# channel-link-test-board.net
KiCad netlist of a schematic drawn in EAGLE
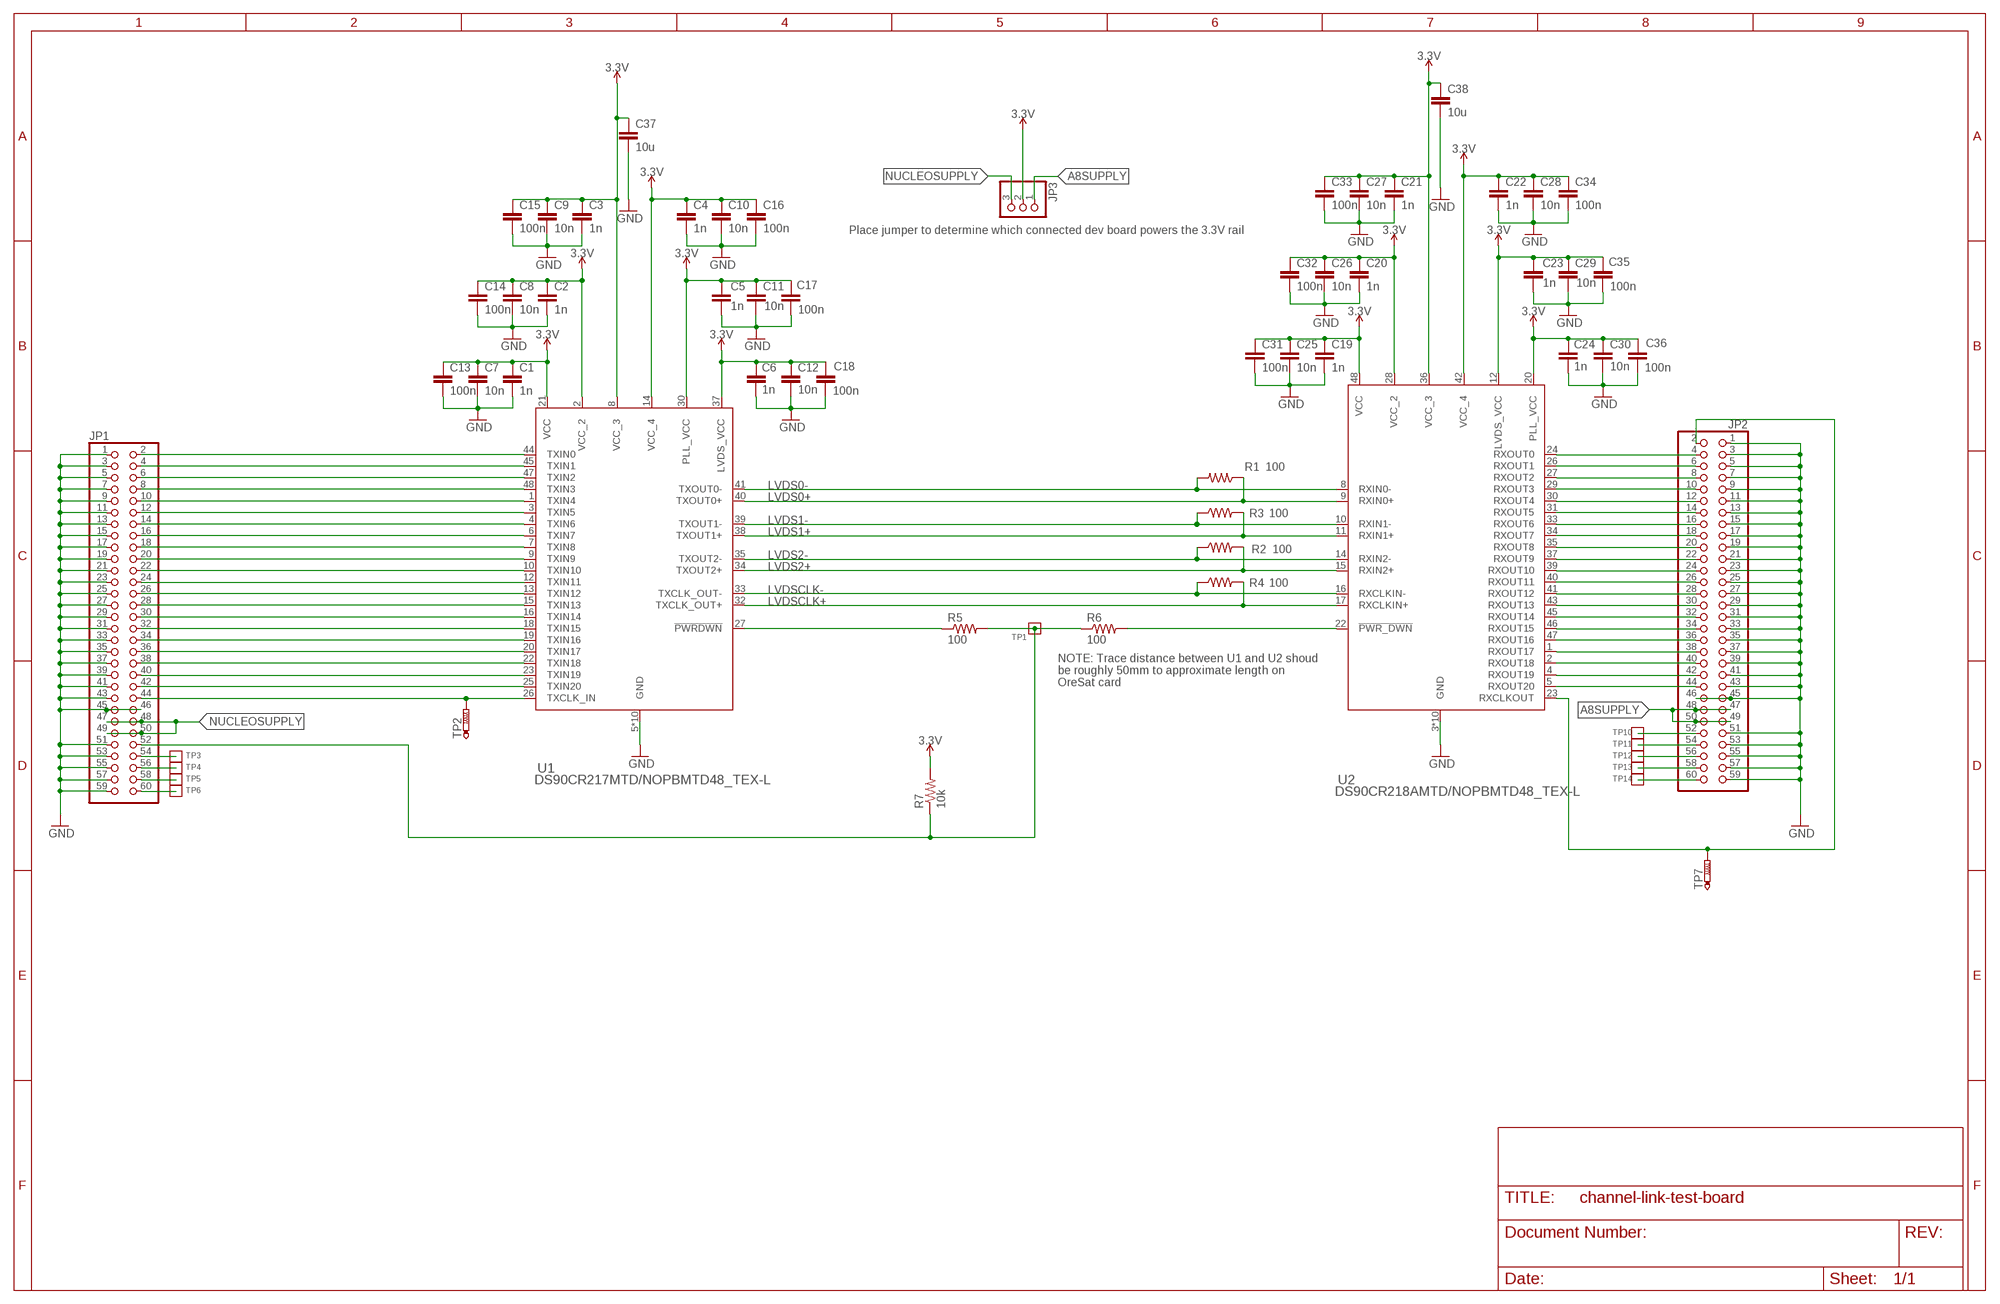
[diagram p0: schematic, sheet 1]

(export (version "E")
  (design (tool "Eeschema 10.0.6"))
  (components
    (comp (ref "C1")
      (value "1n")
      (footprint "eagle-import:.0402-C-NOSILK")
      (fields (field (name "MFR") "Murata") (field (name "MPN") "GRM155R71H102KA01J"))
      (libsource (lib "eagle-import") (part "C-EU0402-C-NOSILK"))
    )
    (comp (ref "C2")
      (value "1n")
      (footprint "eagle-import:.0402-C-NOSILK")
      (fields (field (name "MFR") "Murata") (field (name "MPN") "GRM155R71H102KA01J"))
      (libsource (lib "eagle-import") (part "C-EU0402-C-NOSILK"))
    )
    (comp (ref "C3")
      (value "1n")
      (footprint "eagle-import:.0402-C-NOSILK")
      (fields (field (name "MFR") "Murata") (field (name "MPN") "GRM155R71H102KA01J"))
      (libsource (lib "eagle-import") (part "C-EU0402-C-NOSILK"))
    )
    (comp (ref "C4")
      (value "1n")
      (footprint "eagle-import:.0402-C-NOSILK")
      (fields (field (name "MFR") "Murata") (field (name "MPN") "GRM155R71H102KA01J"))
      (libsource (lib "eagle-import") (part "C-EU0402-C-NOSILK"))
    )
    (comp (ref "C5")
      (value "1n")
      (footprint "eagle-import:.0402-C-NOSILK")
      (fields (field (name "MFR") "Murata") (field (name "MPN") "GRM155R71H102KA01J"))
      (libsource (lib "eagle-import") (part "C-EU0402-C-NOSILK"))
    )
    (comp (ref "C6")
      (value "1n")
      (footprint "eagle-import:.0402-C-NOSILK")
      (fields (field (name "MFR") "Murata") (field (name "MPN") "GRM155R71H102KA01J"))
      (libsource (lib "eagle-import") (part "C-EU0402-C-NOSILK"))
    )
    (comp (ref "C7")
      (value "10n")
      (footprint "eagle-import:.0603-C-NOSILK")
      (fields (field (name "MFR") "Kemet") (field (name "MPN") "C0603C103M5RACTU"))
      (libsource (lib "eagle-import") (part "C-EU0603-C-NOSILK"))
    )
    (comp (ref "C8")
      (value "10n")
      (footprint "eagle-import:.0603-C-NOSILK")
      (fields (field (name "MFR") "Kemet") (field (name "MPN") "C0603C103M5RACTU"))
      (libsource (lib "eagle-import") (part "C-EU0603-C-NOSILK"))
    )
    (comp (ref "C9")
      (value "10n")
      (footprint "eagle-import:.0603-C-NOSILK")
      (fields (field (name "MFR") "Kemet") (field (name "MPN") "C0603C103M5RACTU"))
      (libsource (lib "eagle-import") (part "C-EU0603-C-NOSILK"))
    )
    (comp (ref "C10")
      (value "10n")
      (footprint "eagle-import:.0603-C-NOSILK")
      (fields (field (name "MFR") "Kemet") (field (name "MPN") "C0603C103M5RACTU"))
      (libsource (lib "eagle-import") (part "C-EU0603-C-NOSILK"))
    )
    (comp (ref "C11")
      (value "10n")
      (footprint "eagle-import:.0603-C-NOSILK")
      (fields (field (name "MFR") "Kemet") (field (name "MPN") "C0603C103M5RACTU"))
      (libsource (lib "eagle-import") (part "C-EU0603-C-NOSILK"))
    )
    (comp (ref "C12")
      (value "10n")
      (footprint "eagle-import:.0402-C-NOSILK")
      (fields (field (name "MFR") "Kemet") (field (name "MPN") "C0603C103M5RACTU"))
      (libsource (lib "eagle-import") (part "C-EU0402-C-NOSILK"))
    )
    (comp (ref "C13")
      (value "100n")
      (footprint "eagle-import:.0805-C-NOSILK")
      (fields (field (name "MFR") "Kemet") (field (name "MPN") "C0805C104Z5VACTU"))
      (libsource (lib "eagle-import") (part "C-EU0805-C-NOSILK"))
    )
    (comp (ref "C14")
      (value "100n")
      (footprint "eagle-import:.0402-C-NOSILK")
      (fields (field (name "MFR") "Kemet") (field (name "MPN") "C0805C104Z5VACTU"))
      (libsource (lib "eagle-import") (part "C-EU0402-C-NOSILK"))
    )
    (comp (ref "C15")
      (value "100n")
      (footprint "eagle-import:.0805-C-NOSILK")
      (fields (field (name "MFR") "Kemet") (field (name "MPN") "C0805C104Z5VACTU"))
      (libsource (lib "eagle-import") (part "C-EU0805-C-NOSILK"))
    )
    (comp (ref "C16")
      (value "100n")
      (footprint "eagle-import:.0805-C-NOSILK")
      (fields (field (name "MFR") "Kemet") (field (name "MPN") "C0805C104Z5VACTU"))
      (libsource (lib "eagle-import") (part "C-EU0805-C-NOSILK"))
    )
    (comp (ref "C17")
      (value "100n")
      (footprint "eagle-import:.0805-C-NOSILK")
      (fields (field (name "MFR") "Kemet") (field (name "MPN") "C0805C104Z5VACTU"))
      (libsource (lib "eagle-import") (part "C-EU0805-C-NOSILK"))
    )
    (comp (ref "C18")
      (value "100n")
      (footprint "eagle-import:.0805-C-NOSILK")
      (fields (field (name "MFR") "Kemet") (field (name "MPN") "C0805C104Z5VACTU"))
      (libsource (lib "eagle-import") (part "C-EU0805-C-NOSILK"))
    )
    (comp (ref "C19")
      (value "1n")
      (footprint "eagle-import:.0402-C-NOSILK")
      (fields (field (name "MFR") "Murata") (field (name "MPN") "GRM155R71H102KA01J"))
      (libsource (lib "eagle-import") (part "C-EU0402-C-NOSILK"))
    )
    (comp (ref "C20")
      (value "1n")
      (footprint "eagle-import:.0402-C-NOSILK")
      (fields (field (name "MFR") "Murata") (field (name "MPN") "GRM155R71H102KA01J"))
      (libsource (lib "eagle-import") (part "C-EU0402-C-NOSILK"))
    )
    (comp (ref "C21")
      (value "1n")
      (footprint "eagle-import:.0402-C-NOSILK")
      (fields (field (name "MFR") "Murata") (field (name "MPN") "GRM155R71H102KA01J"))
      (libsource (lib "eagle-import") (part "C-EU0402-C-NOSILK"))
    )
    (comp (ref "C22")
      (value "1n")
      (footprint "eagle-import:.0402-C-NOSILK")
      (fields (field (name "MFR") "Murata") (field (name "MPN") "GRM155R71H102KA01J"))
      (libsource (lib "eagle-import") (part "C-EU0402-C-NOSILK"))
    )
    (comp (ref "C23")
      (value "1n")
      (footprint "eagle-import:.0402-C-NOSILK")
      (fields (field (name "MFR") "Murata") (field (name "MPN") "GRM155R71H102KA01J"))
      (libsource (lib "eagle-import") (part "C-EU0402-C-NOSILK"))
    )
    (comp (ref "C24")
      (value "1n")
      (footprint "eagle-import:.0402-C-NOSILK")
      (fields (field (name "MFR") "Murata") (field (name "MPN") "GRM155R71H102KA01J"))
      (libsource (lib "eagle-import") (part "C-EU0402-C-NOSILK"))
    )
    (comp (ref "C25")
      (value "10n")
      (footprint "eagle-import:.0402-C-NOSILK")
      (fields (field (name "MFR") "Kemet") (field (name "MPN") "C0603C103M5RACTU"))
      (libsource (lib "eagle-import") (part "C-EU0402-C-NOSILK"))
    )
    (comp (ref "C26")
      (value "10n")
      (footprint "eagle-import:.0603-C-NOSILK")
      (fields (field (name "MFR") "Kemet") (field (name "MPN") "C0603C103M5RACTU"))
      (libsource (lib "eagle-import") (part "C-EU0603-C-NOSILK"))
    )
    (comp (ref "C27")
      (value "10n")
      (footprint "eagle-import:.0603-C-NOSILK")
      (fields (field (name "MFR") "Kemet") (field (name "MPN") "C0603C103M5RACTU"))
      (libsource (lib "eagle-import") (part "C-EU0603-C-NOSILK"))
    )
    (comp (ref "C28")
      (value "10n")
      (footprint "eagle-import:.0603-C-NOSILK")
      (fields (field (name "MFR") "Kemet") (field (name "MPN") "C0603C103M5RACTU"))
      (libsource (lib "eagle-import") (part "C-EU0603-C-NOSILK"))
    )
    (comp (ref "C29")
      (value "10n")
      (footprint "eagle-import:.0603-C-NOSILK")
      (fields (field (name "MFR") "Kemet") (field (name "MPN") "C0603C103M5RACTU"))
      (libsource (lib "eagle-import") (part "C-EU0603-C-NOSILK"))
    )
    (comp (ref "C30")
      (value "10n")
      (footprint "eagle-import:.0603-C-NOSILK")
      (fields (field (name "MFR") "Kemet") (field (name "MPN") "C0603C103M5RACTU"))
      (libsource (lib "eagle-import") (part "C-EU0603-C-NOSILK"))
    )
    (comp (ref "C31")
      (value "100n")
      (footprint "eagle-import:.0402-C-NOSILK")
      (fields (field (name "MFR") "Kemet") (field (name "MPN") "C0805C104Z5VACTU"))
      (libsource (lib "eagle-import") (part "C-EU0402-C-NOSILK"))
    )
    (comp (ref "C32")
      (value "100n")
      (footprint "eagle-import:.0805-C-NOSILK")
      (fields (field (name "MFR") "Kemet") (field (name "MPN") "C0805C104Z5VACTU"))
      (libsource (lib "eagle-import") (part "C-EU0805-C-NOSILK"))
    )
    (comp (ref "C33")
      (value "100n")
      (footprint "eagle-import:.0805-C-NOSILK")
      (fields (field (name "MFR") "Kemet") (field (name "MPN") "C0805C104Z5VACTU"))
      (libsource (lib "eagle-import") (part "C-EU0805-C-NOSILK"))
    )
    (comp (ref "C34")
      (value "100n")
      (footprint "eagle-import:.0805-C-NOSILK")
      (fields (field (name "MFR") "Kemet") (field (name "MPN") "C0805C104Z5VACTU"))
      (libsource (lib "eagle-import") (part "C-EU0805-C-NOSILK"))
    )
    (comp (ref "C35")
      (value "100n")
      (footprint "eagle-import:.0805-C-NOSILK")
      (fields (field (name "MFR") "Kemet") (field (name "MPN") "C0805C104Z5VACTU"))
      (libsource (lib "eagle-import") (part "C-EU0805-C-NOSILK"))
    )
    (comp (ref "C36")
      (value "100n")
      (footprint "eagle-import:.0805-C-NOSILK")
      (fields (field (name "MFR") "Kemet") (field (name "MPN") "C0805C104Z5VACTU"))
      (libsource (lib "eagle-import") (part "C-EU0805-C-NOSILK"))
    )
    (comp (ref "C37")
      (value "10u")
      (footprint "eagle-import:.0603-C-NOSILK")
      (fields (field (name "MFR") "Murata") (field (name "MPN") "GRM188R61A106KE69J"))
      (libsource (lib "eagle-import") (part "C-EU0603-C-NOSILK"))
    )
    (comp (ref "C38")
      (value "10u")
      (footprint "eagle-import:.0603-C-NOSILK")
      (fields (field (name "MFR") "Murata") (field (name "MPN") "GRM188R61A106KE69J"))
      (libsource (lib "eagle-import") (part "C-EU0603-C-NOSILK"))
    )
    (comp (ref "JP1")
      (value "PINHD-2X30")
      (footprint "eagle-import:2X30")
      (fields (field (name "MFR") "Amphenol") (field (name "MPN") "71918-160LF"))
      (libsource (lib "eagle-import") (part "PINHD-2X30"))
    )
    (comp (ref "JP2")
      (value "PINHD-2X30")
      (footprint "eagle-import:2X30")
      (fields (field (name "MFR") "Amphenol") (field (name "MPN") "71918-160LF"))
      (libsource (lib "eagle-import") (part "PINHD-2X30"))
    )
    (comp (ref "JP3")
      (value "PINHD-1X3")
      (footprint "eagle-import:1X03")
      (fields (field (name "MFR") "Wurth") (field (name "MPN") "61300311121"))
      (libsource (lib "eagle-import") (part "PINHD-1X3"))
    )
    (comp (ref "R1")
      (value "100")
      (footprint "eagle-import:.0201-C-NOSILK")
      (fields (field (name "MFR") "Yageo") (field (name "MPN") "RC0201FR-07100RL"))
      (libsource (lib "eagle-import") (part "R-US_0201-C-NOSILK"))
    )
    (comp (ref "R2")
      (value "100")
      (footprint "eagle-import:.0201-C-NOSILK")
      (fields (field (name "MFR") "Yageo") (field (name "MPN") "RC0201FR-07100RL"))
      (libsource (lib "eagle-import") (part "R-US_0201-C-NOSILK"))
    )
    (comp (ref "R3")
      (value "100")
      (footprint "eagle-import:.0201-C-NOSILK")
      (fields (field (name "MFR") "Yageo") (field (name "MPN") "RC0201FR-07100RL"))
      (libsource (lib "eagle-import") (part "R-US_0201-C-NOSILK"))
    )
    (comp (ref "R4")
      (value "100")
      (footprint "eagle-import:.0201-C-NOSILK")
      (fields (field (name "MFR") "Yageo") (field (name "MPN") "RC0201FR-07100RL"))
      (libsource (lib "eagle-import") (part "R-US_0201-C-NOSILK"))
    )
    (comp (ref "R5")
      (value "100")
      (footprint "eagle-import:.0603-C-NOSILK")
      (fields (field (name "MFR") "Yageo") (field (name "MPN") "RC0603FR-07100RL"))
      (libsource (lib "eagle-import") (part "R-US_0603-C-NOSILK"))
    )
    (comp (ref "R6")
      (value "100")
      (footprint "eagle-import:.0603-C-NOSILK")
      (fields (field (name "MFR") "Yageo") (field (name "MPN") "RC0603FR-07100RL"))
      (libsource (lib "eagle-import") (part "R-US_0603-C-NOSILK"))
    )
    (comp (ref "R7")
      (value "10k")
      (footprint "eagle-import:.0603-C-NOSILK")
      (fields (field (name "MFR") "Yageo") (field (name "MPN") "RC0603FR-0710KL"))
      (libsource (lib "eagle-import") (part "R-US_0603-C-NOSILK"))
    )
    (comp (ref "TP1")
      (value "TEST-POINT-LARGE-SQUARE")
      (footprint "eagle-import:1X01")
      (libsource (lib "eagle-import") (part "TEST-POINT-LARGE-SQUARE"))
    )
    (comp (ref "TP2")
      (value "PTR1B2,54")
      (footprint "eagle-import:B2,54")
      (libsource (lib "eagle-import") (part "PTR1B2,54"))
    )
    (comp (ref "TP3")
      (value "TEST-POINT-LARGE-SQUARE")
      (footprint "eagle-import:1X01")
      (libsource (lib "eagle-import") (part "TEST-POINT-LARGE-SQUARE"))
    )
    (comp (ref "TP4")
      (value "TEST-POINT-LARGE-SQUARE")
      (footprint "eagle-import:1X01")
      (libsource (lib "eagle-import") (part "TEST-POINT-LARGE-SQUARE"))
    )
    (comp (ref "TP5")
      (value "TEST-POINT-LARGE-SQUARE")
      (footprint "eagle-import:1X01")
      (libsource (lib "eagle-import") (part "TEST-POINT-LARGE-SQUARE"))
    )
    (comp (ref "TP6")
      (value "TEST-POINT-LARGE-SQUARE")
      (footprint "eagle-import:1X01")
      (libsource (lib "eagle-import") (part "TEST-POINT-LARGE-SQUARE"))
    )
    (comp (ref "TP7")
      (value "PTR1B2,54")
      (footprint "eagle-import:B2,54")
      (libsource (lib "eagle-import") (part "PTR1B2,54"))
    )
    (comp (ref "TP10")
      (value "TEST-POINT-LARGE-SQUARE")
      (footprint "eagle-import:1X01")
      (libsource (lib "eagle-import") (part "TEST-POINT-LARGE-SQUARE"))
    )
    (comp (ref "TP11")
      (value "TEST-POINT-LARGE-SQUARE")
      (footprint "eagle-import:1X01")
      (libsource (lib "eagle-import") (part "TEST-POINT-LARGE-SQUARE"))
    )
    (comp (ref "TP12")
      (value "TEST-POINT-LARGE-SQUARE")
      (footprint "eagle-import:1X01")
      (libsource (lib "eagle-import") (part "TEST-POINT-LARGE-SQUARE"))
    )
    (comp (ref "TP13")
      (value "TEST-POINT-LARGE-SQUARE")
      (footprint "eagle-import:1X01")
      (libsource (lib "eagle-import") (part "TEST-POINT-LARGE-SQUARE"))
    )
    (comp (ref "TP14")
      (value "TEST-POINT-LARGE-SQUARE")
      (footprint "eagle-import:1X01")
      (libsource (lib "eagle-import") (part "TEST-POINT-LARGE-SQUARE"))
    )
    (comp (ref "U1")
      (value "DS90CR217MTD/NOPBMTD48_TEX-L")
      (footprint "eagle-import:MTD48_TEX-L")
      (fields (field (name "MFR") "Texas Instruments") (field (name "MPN") "DS90CR218AMTD/NOPB"))
      (libsource (lib "eagle-import") (part "DS90CR217MTD/NOPBMTD48_TEX-L"))
    )
    (comp (ref "U2")
      (value "DS90CR218AMTD/NOPBMTD48_TEX-L")
      (footprint "eagle-import:MTD48_TEX-L")
      (fields (field (name "MFR") "Texas Instruments") (field (name "MPN") "DS90CR218AMTD/NOPB"))
      (libsource (lib "eagle-import") (part "DS90CR218AMTD/NOPBMTD48_TEX-L"))
    )
  )
  (nets
    (net (code "1") (name "/LVDS0+") (class "Default")
      (node (ref "R1") (pin "1") (pinfunction "1_1") (pintype "passive"))
      (node (ref "U1") (pin "40") (pinfunction "TXOUT0+_40") (pintype "output"))
      (node (ref "U2") (pin "9") (pinfunction "RXIN0+_9") (pintype "input"))
    )
    (net (code "2") (name "/LVDS0-") (class "Default")
      (node (ref "R1") (pin "2") (pinfunction "2_2") (pintype "passive"))
      (node (ref "U1") (pin "41") (pinfunction "TXOUT0-_41") (pintype "output"))
      (node (ref "U2") (pin "8") (pinfunction "RXIN0-_8") (pintype "input"))
    )
    (net (code "3") (name "/LVDS1+") (class "Default")
      (node (ref "R3") (pin "2") (pinfunction "2_2") (pintype "passive"))
      (node (ref "U1") (pin "38") (pinfunction "TXOUT1+_38") (pintype "output"))
      (node (ref "U2") (pin "11") (pinfunction "RXIN1+_11") (pintype "input"))
    )
    (net (code "4") (name "/LVDS1-") (class "Default")
      (node (ref "R3") (pin "1") (pinfunction "1_1") (pintype "passive"))
      (node (ref "U1") (pin "39") (pinfunction "TXOUT1-_39") (pintype "output"))
      (node (ref "U2") (pin "10") (pinfunction "RXIN1-_10") (pintype "input"))
    )
    (net (code "5") (name "/LVDS2+") (class "Default")
      (node (ref "R2") (pin "2") (pinfunction "2_2") (pintype "passive"))
      (node (ref "U1") (pin "34") (pinfunction "TXOUT2+_34") (pintype "output"))
      (node (ref "U2") (pin "15") (pinfunction "RXIN2+_15") (pintype "input"))
    )
    (net (code "6") (name "/LVDS2-") (class "Default")
      (node (ref "R2") (pin "1") (pinfunction "1_1") (pintype "passive"))
      (node (ref "U1") (pin "35") (pinfunction "TXOUT2-_35") (pintype "output"))
      (node (ref "U2") (pin "14") (pinfunction "RXIN2-_14") (pintype "input"))
    )
    (net (code "7") (name "/LVDSCLK+") (class "Default")
      (node (ref "R4") (pin "2") (pinfunction "2_2") (pintype "passive"))
      (node (ref "U1") (pin "32") (pinfunction "TXCLK_OUT+_32") (pintype "output"))
      (node (ref "U2") (pin "17") (pinfunction "RXCLKIN+_17") (pintype "input"))
    )
    (net (code "8") (name "/LVDSCLK-") (class "Default")
      (node (ref "R4") (pin "1") (pinfunction "1_1") (pintype "passive"))
      (node (ref "U1") (pin "33") (pinfunction "TXCLK_OUT-_33") (pintype "output"))
      (node (ref "U2") (pin "16") (pinfunction "RXCLKIN-_16") (pintype "input"))
    )
    (net (code "9") (name "3.3V") (class "Default")
      (node (ref "C1") (pin "1") (pinfunction "1_1") (pintype "passive"))
      (node (ref "C10") (pin "1") (pinfunction "1_1") (pintype "passive"))
      (node (ref "C11") (pin "1") (pinfunction "1_1") (pintype "passive"))
      (node (ref "C12") (pin "1") (pinfunction "1_1") (pintype "passive"))
      (node (ref "C13") (pin "1") (pinfunction "1_1") (pintype "passive"))
      (node (ref "C14") (pin "1") (pinfunction "1_1") (pintype "passive"))
      (node (ref "C15") (pin "1") (pinfunction "1_1") (pintype "passive"))
      (node (ref "C16") (pin "1") (pinfunction "1_1") (pintype "passive"))
      (node (ref "C17") (pin "1") (pinfunction "1_1") (pintype "passive"))
      (node (ref "C18") (pin "1") (pinfunction "1_1") (pintype "passive"))
      (node (ref "C19") (pin "1") (pinfunction "1_1") (pintype "passive"))
      (node (ref "C2") (pin "1") (pinfunction "1_1") (pintype "passive"))
      (node (ref "C20") (pin "1") (pinfunction "1_1") (pintype "passive"))
      (node (ref "C21") (pin "1") (pinfunction "1_1") (pintype "passive"))
      (node (ref "C22") (pin "1") (pinfunction "1_1") (pintype "passive"))
      (node (ref "C23") (pin "1") (pinfunction "1_1") (pintype "passive"))
      (node (ref "C24") (pin "1") (pinfunction "1_1") (pintype "passive"))
      (node (ref "C25") (pin "1") (pinfunction "1_1") (pintype "passive"))
      (node (ref "C26") (pin "1") (pinfunction "1_1") (pintype "passive"))
      (node (ref "C27") (pin "1") (pinfunction "1_1") (pintype "passive"))
      (node (ref "C28") (pin "1") (pinfunction "1_1") (pintype "passive"))
      (node (ref "C29") (pin "1") (pinfunction "1_1") (pintype "passive"))
      (node (ref "C3") (pin "1") (pinfunction "1_1") (pintype "passive"))
      (node (ref "C30") (pin "1") (pinfunction "1_1") (pintype "passive"))
      (node (ref "C31") (pin "1") (pinfunction "1_1") (pintype "passive"))
      (node (ref "C32") (pin "1") (pinfunction "1_1") (pintype "passive"))
      (node (ref "C33") (pin "1") (pinfunction "1_1") (pintype "passive"))
      (node (ref "C34") (pin "1") (pinfunction "1_1") (pintype "passive"))
      (node (ref "C35") (pin "1") (pinfunction "1_1") (pintype "passive"))
      (node (ref "C36") (pin "1") (pinfunction "1_1") (pintype "passive"))
      (node (ref "C37") (pin "1") (pinfunction "1_1") (pintype "passive"))
      (node (ref "C38") (pin "1") (pinfunction "1_1") (pintype "passive"))
      (node (ref "C4") (pin "1") (pinfunction "1_1") (pintype "passive"))
      (node (ref "C5") (pin "1") (pinfunction "1_1") (pintype "passive"))
      (node (ref "C6") (pin "1") (pinfunction "1_1") (pintype "passive"))
      (node (ref "C7") (pin "1") (pinfunction "1_1") (pintype "passive"))
      (node (ref "C8") (pin "1") (pinfunction "1_1") (pintype "passive"))
      (node (ref "C9") (pin "1") (pinfunction "1_1") (pintype "passive"))
      (node (ref "JP3") (pin "2") (pinfunction "2_2") (pintype "passive"))
      (node (ref "R7") (pin "2") (pinfunction "2_2") (pintype "passive"))
      (node (ref "U1") (pin "14") (pinfunction "VCC_4_14") (pintype "power_in"))
      (node (ref "U1") (pin "2") (pinfunction "VCC_2_2") (pintype "power_in"))
      (node (ref "U1") (pin "21") (pinfunction "VCC_21") (pintype "power_in"))
      (node (ref "U1") (pin "30") (pinfunction "PLL_VCC_30") (pintype "power_in"))
      (node (ref "U1") (pin "37") (pinfunction "LVDS_VCC_37") (pintype "passive"))
      (node (ref "U1") (pin "8") (pinfunction "VCC_3_8") (pintype "power_in"))
      (node (ref "U2") (pin "12") (pinfunction "LVDS_VCC_12") (pintype "power_in"))
      (node (ref "U2") (pin "20") (pinfunction "PLL_VCC_20") (pintype "power_in"))
      (node (ref "U2") (pin "28") (pinfunction "VCC_2_28") (pintype "power_in"))
      (node (ref "U2") (pin "36") (pinfunction "VCC_3_36") (pintype "power_in"))
      (node (ref "U2") (pin "42") (pinfunction "VCC_4_42") (pintype "power_in"))
      (node (ref "U2") (pin "48") (pinfunction "VCC_48") (pintype "power_in"))
    )
    (net (code "10") (name "A8SUPPLY") (class "Default")
      (node (ref "JP2") (pin "47") (pinfunction "47_47") (pintype "passive"))
      (node (ref "JP2") (pin "48") (pinfunction "48_48") (pintype "passive"))
      (node (ref "JP2") (pin "49") (pinfunction "49_49") (pintype "passive"))
      (node (ref "JP2") (pin "50") (pinfunction "50_50") (pintype "passive"))
      (node (ref "JP3") (pin "1") (pinfunction "1_1") (pintype "passive"))
    )
    (net (code "11") (name "GND") (class "Default")
      (node (ref "C1") (pin "2") (pinfunction "2_2") (pintype "passive"))
      (node (ref "C10") (pin "2") (pinfunction "2_2") (pintype "passive"))
      (node (ref "C11") (pin "2") (pinfunction "2_2") (pintype "passive"))
      (node (ref "C12") (pin "2") (pinfunction "2_2") (pintype "passive"))
      (node (ref "C13") (pin "2") (pinfunction "2_2") (pintype "passive"))
      (node (ref "C14") (pin "2") (pinfunction "2_2") (pintype "passive"))
      (node (ref "C15") (pin "2") (pinfunction "2_2") (pintype "passive"))
      (node (ref "C16") (pin "2") (pinfunction "2_2") (pintype "passive"))
      (node (ref "C17") (pin "2") (pinfunction "2_2") (pintype "passive"))
      (node (ref "C18") (pin "2") (pinfunction "2_2") (pintype "passive"))
      (node (ref "C19") (pin "2") (pinfunction "2_2") (pintype "passive"))
      (node (ref "C2") (pin "2") (pinfunction "2_2") (pintype "passive"))
      (node (ref "C20") (pin "2") (pinfunction "2_2") (pintype "passive"))
      (node (ref "C21") (pin "2") (pinfunction "2_2") (pintype "passive"))
      (node (ref "C22") (pin "2") (pinfunction "2_2") (pintype "passive"))
      (node (ref "C23") (pin "2") (pinfunction "2_2") (pintype "passive"))
      (node (ref "C24") (pin "2") (pinfunction "2_2") (pintype "passive"))
      (node (ref "C25") (pin "2") (pinfunction "2_2") (pintype "passive"))
      (node (ref "C26") (pin "2") (pinfunction "2_2") (pintype "passive"))
      (node (ref "C27") (pin "2") (pinfunction "2_2") (pintype "passive"))
      (node (ref "C28") (pin "2") (pinfunction "2_2") (pintype "passive"))
      (node (ref "C29") (pin "2") (pinfunction "2_2") (pintype "passive"))
      (node (ref "C3") (pin "2") (pinfunction "2_2") (pintype "passive"))
      (node (ref "C30") (pin "2") (pinfunction "2_2") (pintype "passive"))
      (node (ref "C31") (pin "2") (pinfunction "2_2") (pintype "passive"))
      (node (ref "C32") (pin "2") (pinfunction "2_2") (pintype "passive"))
      (node (ref "C33") (pin "2") (pinfunction "2_2") (pintype "passive"))
      (node (ref "C34") (pin "2") (pinfunction "2_2") (pintype "passive"))
      (node (ref "C35") (pin "2") (pinfunction "2_2") (pintype "passive"))
      (node (ref "C36") (pin "2") (pinfunction "2_2") (pintype "passive"))
      (node (ref "C37") (pin "2") (pinfunction "2_2") (pintype "passive"))
      (node (ref "C38") (pin "2") (pinfunction "2_2") (pintype "passive"))
      (node (ref "C4") (pin "2") (pinfunction "2_2") (pintype "passive"))
      (node (ref "C5") (pin "2") (pinfunction "2_2") (pintype "passive"))
      (node (ref "C6") (pin "2") (pinfunction "2_2") (pintype "passive"))
      (node (ref "C7") (pin "2") (pinfunction "2_2") (pintype "passive"))
      (node (ref "C8") (pin "2") (pinfunction "2_2") (pintype "passive"))
      (node (ref "C9") (pin "2") (pinfunction "2_2") (pintype "passive"))
      (node (ref "JP1") (pin "1") (pinfunction "1_1") (pintype "passive"))
      (node (ref "JP1") (pin "11") (pinfunction "11_11") (pintype "passive"))
      (node (ref "JP1") (pin "13") (pinfunction "13_13") (pintype "passive"))
      (node (ref "JP1") (pin "15") (pinfunction "15_15") (pintype "passive"))
      (node (ref "JP1") (pin "17") (pinfunction "17_17") (pintype "passive"))
      (node (ref "JP1") (pin "19") (pinfunction "19_19") (pintype "passive"))
      (node (ref "JP1") (pin "21") (pinfunction "21_21") (pintype "passive"))
      (node (ref "JP1") (pin "23") (pinfunction "23_23") (pintype "passive"))
      (node (ref "JP1") (pin "25") (pinfunction "25_25") (pintype "passive"))
      (node (ref "JP1") (pin "27") (pinfunction "27_27") (pintype "passive"))
      (node (ref "JP1") (pin "29") (pinfunction "29_29") (pintype "passive"))
      (node (ref "JP1") (pin "3") (pinfunction "3_3") (pintype "passive"))
      (node (ref "JP1") (pin "31") (pinfunction "31_31") (pintype "passive"))
      (node (ref "JP1") (pin "33") (pinfunction "33_33") (pintype "passive"))
      (node (ref "JP1") (pin "35") (pinfunction "35_35") (pintype "passive"))
      (node (ref "JP1") (pin "37") (pinfunction "37_37") (pintype "passive"))
      (node (ref "JP1") (pin "39") (pinfunction "39_39") (pintype "passive"))
      (node (ref "JP1") (pin "41") (pinfunction "41_41") (pintype "passive"))
      (node (ref "JP1") (pin "43") (pinfunction "43_43") (pintype "passive"))
      (node (ref "JP1") (pin "45") (pinfunction "45_45") (pintype "passive"))
      (node (ref "JP1") (pin "46") (pinfunction "46_46") (pintype "passive"))
      (node (ref "JP1") (pin "5") (pinfunction "5_5") (pintype "passive"))
      (node (ref "JP1") (pin "51") (pinfunction "51_51") (pintype "passive"))
      (node (ref "JP1") (pin "53") (pinfunction "53_53") (pintype "passive"))
      (node (ref "JP1") (pin "55") (pinfunction "55_55") (pintype "passive"))
      (node (ref "JP1") (pin "57") (pinfunction "57_57") (pintype "passive"))
      (node (ref "JP1") (pin "59") (pinfunction "59_59") (pintype "passive"))
      (node (ref "JP1") (pin "7") (pinfunction "7_7") (pintype "passive"))
      (node (ref "JP1") (pin "9") (pinfunction "9_9") (pintype "passive"))
      (node (ref "JP2") (pin "1") (pinfunction "1_1") (pintype "passive"))
      (node (ref "JP2") (pin "11") (pinfunction "11_11") (pintype "passive"))
      (node (ref "JP2") (pin "13") (pinfunction "13_13") (pintype "passive"))
      (node (ref "JP2") (pin "15") (pinfunction "15_15") (pintype "passive"))
      (node (ref "JP2") (pin "17") (pinfunction "17_17") (pintype "passive"))
      (node (ref "JP2") (pin "19") (pinfunction "19_19") (pintype "passive"))
      (node (ref "JP2") (pin "21") (pinfunction "21_21") (pintype "passive"))
      (node (ref "JP2") (pin "23") (pinfunction "23_23") (pintype "passive"))
      (node (ref "JP2") (pin "25") (pinfunction "25_25") (pintype "passive"))
      (node (ref "JP2") (pin "27") (pinfunction "27_27") (pintype "passive"))
      (node (ref "JP2") (pin "29") (pinfunction "29_29") (pintype "passive"))
      (node (ref "JP2") (pin "3") (pinfunction "3_3") (pintype "passive"))
      (node (ref "JP2") (pin "31") (pinfunction "31_31") (pintype "passive"))
      (node (ref "JP2") (pin "33") (pinfunction "33_33") (pintype "passive"))
      (node (ref "JP2") (pin "35") (pinfunction "35_35") (pintype "passive"))
      (node (ref "JP2") (pin "37") (pinfunction "37_37") (pintype "passive"))
      (node (ref "JP2") (pin "39") (pinfunction "39_39") (pintype "passive"))
      (node (ref "JP2") (pin "41") (pinfunction "41_41") (pintype "passive"))
      (node (ref "JP2") (pin "43") (pinfunction "43_43") (pintype "passive"))
      (node (ref "JP2") (pin "45") (pinfunction "45_45") (pintype "passive"))
      (node (ref "JP2") (pin "46") (pinfunction "46_46") (pintype "passive"))
      (node (ref "JP2") (pin "5") (pinfunction "5_5") (pintype "passive"))
      (node (ref "JP2") (pin "51") (pinfunction "51_51") (pintype "passive"))
      (node (ref "JP2") (pin "53") (pinfunction "53_53") (pintype "passive"))
      (node (ref "JP2") (pin "55") (pinfunction "55_55") (pintype "passive"))
      (node (ref "JP2") (pin "57") (pinfunction "57_57") (pintype "passive"))
      (node (ref "JP2") (pin "59") (pinfunction "59_59") (pintype "passive"))
      (node (ref "JP2") (pin "7") (pinfunction "7_7") (pintype "passive"))
      (node (ref "JP2") (pin "9") (pinfunction "9_9") (pintype "passive"))
      (node (ref "U1") (pin "11") (pinfunction "GND_11") (pintype "power_in"))
      (node (ref "U1") (pin "17") (pinfunction "GND_17") (pintype "power_in"))
      (node (ref "U1") (pin "24") (pinfunction "GND_24") (pintype "power_in"))
      (node (ref "U1") (pin "28") (pinfunction "GND_28") (pintype "power_in"))
      (node (ref "U1") (pin "29") (pinfunction "GND_29") (pintype "power_in"))
      (node (ref "U1") (pin "31") (pinfunction "GND_31") (pintype "power_in"))
      (node (ref "U1") (pin "36") (pinfunction "GND_36") (pintype "power_in"))
      (node (ref "U1") (pin "42") (pinfunction "GND_42") (pintype "power_in"))
      (node (ref "U1") (pin "46") (pinfunction "GND_46") (pintype "power_in"))
      (node (ref "U1") (pin "5") (pinfunction "GND_5") (pintype "power_in"))
      (node (ref "U2") (pin "13") (pinfunction "GND_13") (pintype "power_in"))
      (node (ref "U2") (pin "18") (pinfunction "GND_18") (pintype "power_in"))
      (node (ref "U2") (pin "19") (pinfunction "GND_19") (pintype "power_in"))
      (node (ref "U2") (pin "21") (pinfunction "GND_21") (pintype "power_in"))
      (node (ref "U2") (pin "25") (pinfunction "GND_25") (pintype "power_in"))
      (node (ref "U2") (pin "3") (pinfunction "GND_3") (pintype "power_in"))
      (node (ref "U2") (pin "32") (pinfunction "GND_32") (pintype "power_in"))
      (node (ref "U2") (pin "38") (pinfunction "GND_38") (pintype "power_in"))
      (node (ref "U2") (pin "44") (pinfunction "GND_44") (pintype "power_in"))
      (node (ref "U2") (pin "7") (pinfunction "GND_7") (pintype "power_in"))
    )
    (net (code "12") (name "NUCLEOSUPPLY") (class "Default")
      (node (ref "JP1") (pin "47") (pinfunction "47_47") (pintype "passive"))
      (node (ref "JP1") (pin "48") (pinfunction "48_48") (pintype "passive"))
      (node (ref "JP1") (pin "49") (pinfunction "49_49") (pintype "passive"))
      (node (ref "JP1") (pin "50") (pinfunction "50_50") (pintype "passive"))
      (node (ref "JP3") (pin "3") (pinfunction "3_3") (pintype "passive"))
    )
    (net (code "13") (name "Net-(JP1-Pad52)") (class "Default")
      (node (ref "JP1") (pin "52") (pinfunction "52_52") (pintype "passive"))
      (node (ref "R5") (pin "2") (pinfunction "2_2") (pintype "passive"))
      (node (ref "R6") (pin "1") (pinfunction "1_1") (pintype "passive"))
      (node (ref "R7") (pin "1") (pinfunction "1_1") (pintype "passive"))
      (node (ref "TP1") (pin "1") (pinfunction "1_1") (pintype "passive"))
    )
    (net (code "14") (name "Net-(JP1-Pad54)") (class "Default")
      (node (ref "JP1") (pin "54") (pinfunction "54_54") (pintype "passive"))
      (node (ref "TP3") (pin "1") (pinfunction "1_1") (pintype "passive"))
    )
    (net (code "15") (name "Net-(JP1-Pad56)") (class "Default")
      (node (ref "JP1") (pin "56") (pinfunction "56_56") (pintype "passive"))
      (node (ref "TP4") (pin "1") (pinfunction "1_1") (pintype "passive"))
    )
    (net (code "16") (name "Net-(JP1-Pad58)") (class "Default")
      (node (ref "JP1") (pin "58") (pinfunction "58_58") (pintype "passive"))
      (node (ref "TP5") (pin "1") (pinfunction "1_1") (pintype "passive"))
    )
    (net (code "17") (name "Net-(JP1-Pad60)") (class "Default")
      (node (ref "JP1") (pin "60") (pinfunction "60_60") (pintype "passive"))
      (node (ref "TP6") (pin "1") (pinfunction "1_1") (pintype "passive"))
    )
    (net (code "18") (name "Net-(JP2-Pad52)") (class "Default")
      (node (ref "JP2") (pin "52") (pinfunction "52_52") (pintype "passive"))
      (node (ref "TP10") (pin "1") (pinfunction "1_1") (pintype "passive"))
    )
    (net (code "19") (name "Net-(JP2-Pad54)") (class "Default")
      (node (ref "JP2") (pin "54") (pinfunction "54_54") (pintype "passive"))
      (node (ref "TP11") (pin "1") (pinfunction "1_1") (pintype "passive"))
    )
    (net (code "20") (name "Net-(JP2-Pad56)") (class "Default")
      (node (ref "JP2") (pin "56") (pinfunction "56_56") (pintype "passive"))
      (node (ref "TP12") (pin "1") (pinfunction "1_1") (pintype "passive"))
    )
    (net (code "21") (name "Net-(JP2-Pad58)") (class "Default")
      (node (ref "JP2") (pin "58") (pinfunction "58_58") (pintype "passive"))
      (node (ref "TP13") (pin "1") (pinfunction "1_1") (pintype "passive"))
    )
    (net (code "22") (name "Net-(JP2-Pad60)") (class "Default")
      (node (ref "JP2") (pin "60") (pinfunction "60_60") (pintype "passive"))
      (node (ref "TP14") (pin "1") (pinfunction "1_1") (pintype "passive"))
    )
    (net (code "23") (name "Net-(U1-TXCLK_IN)") (class "Default")
      (node (ref "JP1") (pin "44") (pinfunction "44_44") (pintype "passive"))
      (node (ref "TP2") (pin "TP") (pinfunction "TP_TP") (pintype "input"))
      (node (ref "U1") (pin "26") (pinfunction "TXCLK_IN_26") (pintype "passive"))
    )
    (net (code "24") (name "Net-(U1-TXIN0)") (class "Default")
      (node (ref "JP1") (pin "2") (pinfunction "2_2") (pintype "passive"))
      (node (ref "U1") (pin "44") (pinfunction "TXIN0_44") (pintype "input"))
    )
    (net (code "25") (name "Net-(U1-TXIN1)") (class "Default")
      (node (ref "JP1") (pin "4") (pinfunction "4_4") (pintype "passive"))
      (node (ref "U1") (pin "45") (pinfunction "TXIN1_45") (pintype "input"))
    )
    (net (code "26") (name "Net-(U1-TXIN2)") (class "Default")
      (node (ref "JP1") (pin "6") (pinfunction "6_6") (pintype "passive"))
      (node (ref "U1") (pin "47") (pinfunction "TXIN2_47") (pintype "input"))
    )
    (net (code "27") (name "Net-(U1-TXIN3)") (class "Default")
      (node (ref "JP1") (pin "8") (pinfunction "8_8") (pintype "passive"))
      (node (ref "U1") (pin "48") (pinfunction "TXIN3_48") (pintype "input"))
    )
    (net (code "28") (name "Net-(U1-TXIN4)") (class "Default")
      (node (ref "JP1") (pin "10") (pinfunction "10_10") (pintype "passive"))
      (node (ref "U1") (pin "1") (pinfunction "TXIN4_1") (pintype "input"))
    )
    (net (code "29") (name "Net-(U1-TXIN5)") (class "Default")
      (node (ref "JP1") (pin "12") (pinfunction "12_12") (pintype "passive"))
      (node (ref "U1") (pin "3") (pinfunction "TXIN5_3") (pintype "input"))
    )
    (net (code "30") (name "Net-(U1-TXIN6)") (class "Default")
      (node (ref "JP1") (pin "14") (pinfunction "14_14") (pintype "passive"))
      (node (ref "U1") (pin "4") (pinfunction "TXIN6_4") (pintype "input"))
    )
    (net (code "31") (name "Net-(U1-TXIN7)") (class "Default")
      (node (ref "JP1") (pin "16") (pinfunction "16_16") (pintype "passive"))
      (node (ref "U1") (pin "6") (pinfunction "TXIN7_6") (pintype "input"))
    )
    (net (code "32") (name "Net-(U1-TXIN8)") (class "Default")
      (node (ref "JP1") (pin "18") (pinfunction "18_18") (pintype "passive"))
      (node (ref "U1") (pin "7") (pinfunction "TXIN8_7") (pintype "input"))
    )
    (net (code "33") (name "Net-(U1-TXIN9)") (class "Default")
      (node (ref "JP1") (pin "20") (pinfunction "20_20") (pintype "passive"))
      (node (ref "U1") (pin "9") (pinfunction "TXIN9_9") (pintype "input"))
    )
    (net (code "34") (name "Net-(U1-TXIN10)") (class "Default")
      (node (ref "JP1") (pin "22") (pinfunction "22_22") (pintype "passive"))
      (node (ref "U1") (pin "10") (pinfunction "TXIN10_10") (pintype "input"))
    )
    (net (code "35") (name "Net-(U1-TXIN11)") (class "Default")
      (node (ref "JP1") (pin "24") (pinfunction "24_24") (pintype "passive"))
      (node (ref "U1") (pin "12") (pinfunction "TXIN11_12") (pintype "input"))
    )
    (net (code "36") (name "Net-(U1-TXIN12)") (class "Default")
      (node (ref "JP1") (pin "26") (pinfunction "26_26") (pintype "passive"))
      (node (ref "U1") (pin "13") (pinfunction "TXIN12_13") (pintype "input"))
    )
    (net (code "37") (name "Net-(U1-TXIN13)") (class "Default")
      (node (ref "JP1") (pin "28") (pinfunction "28_28") (pintype "passive"))
      (node (ref "U1") (pin "15") (pinfunction "TXIN13_15") (pintype "input"))
    )
    (net (code "38") (name "Net-(U1-TXIN14)") (class "Default")
      (node (ref "JP1") (pin "30") (pinfunction "30_30") (pintype "passive"))
      (node (ref "U1") (pin "16") (pinfunction "TXIN14_16") (pintype "input"))
    )
    (net (code "39") (name "Net-(U1-TXIN15)") (class "Default")
      (node (ref "JP1") (pin "32") (pinfunction "32_32") (pintype "passive"))
      (node (ref "U1") (pin "18") (pinfunction "TXIN15_18") (pintype "input"))
    )
    (net (code "40") (name "Net-(U1-TXIN16)") (class "Default")
      (node (ref "JP1") (pin "34") (pinfunction "34_34") (pintype "passive"))
      (node (ref "U1") (pin "19") (pinfunction "TXIN16_19") (pintype "input"))
    )
    (net (code "41") (name "Net-(U1-TXIN17)") (class "Default")
      (node (ref "JP1") (pin "36") (pinfunction "36_36") (pintype "passive"))
      (node (ref "U1") (pin "20") (pinfunction "TXIN17_20") (pintype "input"))
    )
    (net (code "42") (name "Net-(U1-TXIN18)") (class "Default")
      (node (ref "JP1") (pin "38") (pinfunction "38_38") (pintype "passive"))
      (node (ref "U1") (pin "22") (pinfunction "TXIN18_22") (pintype "input"))
    )
    (net (code "43") (name "Net-(U1-TXIN19)") (class "Default")
      (node (ref "JP1") (pin "40") (pinfunction "40_40") (pintype "passive"))
      (node (ref "U1") (pin "23") (pinfunction "TXIN19_23") (pintype "input"))
    )
    (net (code "44") (name "Net-(U1-TXIN20)") (class "Default")
      (node (ref "JP1") (pin "42") (pinfunction "42_42") (pintype "passive"))
      (node (ref "U1") (pin "25") (pinfunction "TXIN20_25") (pintype "input"))
    )
    (net (code "45") (name "Net-(U1-~{PWRDWN})") (class "Default")
      (node (ref "R5") (pin "1") (pinfunction "1_1") (pintype "passive"))
      (node (ref "U1") (pin "27") (pinfunction "~{PWRDWN}_27") (pintype "passive"))
    )
    (net (code "46") (name "Net-(U2-RXCLKOUT)") (class "Default")
      (node (ref "JP2") (pin "2") (pinfunction "2_2") (pintype "passive"))
      (node (ref "TP7") (pin "TP") (pinfunction "TP_TP") (pintype "input"))
      (node (ref "U2") (pin "23") (pinfunction "RXCLKOUT_23") (pintype "output"))
    )
    (net (code "47") (name "Net-(U2-RXOUT0)") (class "Default")
      (node (ref "JP2") (pin "4") (pinfunction "4_4") (pintype "passive"))
      (node (ref "U2") (pin "24") (pinfunction "RXOUT0_24") (pintype "output"))
    )
    (net (code "48") (name "Net-(U2-RXOUT1)") (class "Default")
      (node (ref "JP2") (pin "6") (pinfunction "6_6") (pintype "passive"))
      (node (ref "U2") (pin "26") (pinfunction "RXOUT1_26") (pintype "output"))
    )
    (net (code "49") (name "Net-(U2-RXOUT2)") (class "Default")
      (node (ref "JP2") (pin "8") (pinfunction "8_8") (pintype "passive"))
      (node (ref "U2") (pin "27") (pinfunction "RXOUT2_27") (pintype "output"))
    )
    (net (code "50") (name "Net-(U2-RXOUT3)") (class "Default")
      (node (ref "JP2") (pin "10") (pinfunction "10_10") (pintype "passive"))
      (node (ref "U2") (pin "29") (pinfunction "RXOUT3_29") (pintype "output"))
    )
    (net (code "51") (name "Net-(U2-RXOUT4)") (class "Default")
      (node (ref "JP2") (pin "12") (pinfunction "12_12") (pintype "passive"))
      (node (ref "U2") (pin "30") (pinfunction "RXOUT4_30") (pintype "output"))
    )
    (net (code "52") (name "Net-(U2-RXOUT5)") (class "Default")
      (node (ref "JP2") (pin "14") (pinfunction "14_14") (pintype "passive"))
      (node (ref "U2") (pin "31") (pinfunction "RXOUT5_31") (pintype "output"))
    )
    (net (code "53") (name "Net-(U2-RXOUT6)") (class "Default")
      (node (ref "JP2") (pin "16") (pinfunction "16_16") (pintype "passive"))
      (node (ref "U2") (pin "33") (pinfunction "RXOUT6_33") (pintype "output"))
    )
    (net (code "54") (name "Net-(U2-RXOUT7)") (class "Default")
      (node (ref "JP2") (pin "18") (pinfunction "18_18") (pintype "passive"))
      (node (ref "U2") (pin "34") (pinfunction "RXOUT7_34") (pintype "output"))
    )
    (net (code "55") (name "Net-(U2-RXOUT8)") (class "Default")
      (node (ref "JP2") (pin "20") (pinfunction "20_20") (pintype "passive"))
      (node (ref "U2") (pin "35") (pinfunction "RXOUT8_35") (pintype "output"))
    )
    (net (code "56") (name "Net-(U2-RXOUT9)") (class "Default")
      (node (ref "JP2") (pin "22") (pinfunction "22_22") (pintype "passive"))
      (node (ref "U2") (pin "37") (pinfunction "RXOUT9_37") (pintype "output"))
    )
    (net (code "57") (name "Net-(U2-RXOUT10)") (class "Default")
      (node (ref "JP2") (pin "24") (pinfunction "24_24") (pintype "passive"))
      (node (ref "U2") (pin "39") (pinfunction "RXOUT10_39") (pintype "output"))
    )
    (net (code "58") (name "Net-(U2-RXOUT11)") (class "Default")
      (node (ref "JP2") (pin "26") (pinfunction "26_26") (pintype "passive"))
      (node (ref "U2") (pin "40") (pinfunction "RXOUT11_40") (pintype "output"))
    )
    (net (code "59") (name "Net-(U2-RXOUT12)") (class "Default")
      (node (ref "JP2") (pin "28") (pinfunction "28_28") (pintype "passive"))
      (node (ref "U2") (pin "41") (pinfunction "RXOUT12_41") (pintype "output"))
    )
    (net (code "60") (name "Net-(U2-RXOUT13)") (class "Default")
      (node (ref "JP2") (pin "30") (pinfunction "30_30") (pintype "passive"))
      (node (ref "U2") (pin "43") (pinfunction "RXOUT13_43") (pintype "output"))
    )
    (net (code "61") (name "Net-(U2-RXOUT14)") (class "Default")
      (node (ref "JP2") (pin "32") (pinfunction "32_32") (pintype "passive"))
      (node (ref "U2") (pin "45") (pinfunction "RXOUT14_45") (pintype "output"))
    )
    (net (code "62") (name "Net-(U2-RXOUT15)") (class "Default")
      (node (ref "JP2") (pin "34") (pinfunction "34_34") (pintype "passive"))
      (node (ref "U2") (pin "46") (pinfunction "RXOUT15_46") (pintype "output"))
    )
    (net (code "63") (name "Net-(U2-RXOUT16)") (class "Default")
      (node (ref "JP2") (pin "36") (pinfunction "36_36") (pintype "passive"))
      (node (ref "U2") (pin "47") (pinfunction "RXOUT16_47") (pintype "output"))
    )
    (net (code "64") (name "Net-(U2-RXOUT17)") (class "Default")
      (node (ref "JP2") (pin "38") (pinfunction "38_38") (pintype "passive"))
      (node (ref "U2") (pin "1") (pinfunction "RXOUT17_1") (pintype "output"))
    )
    (net (code "65") (name "Net-(U2-RXOUT18)") (class "Default")
      (node (ref "JP2") (pin "40") (pinfunction "40_40") (pintype "passive"))
      (node (ref "U2") (pin "2") (pinfunction "RXOUT18_2") (pintype "output"))
    )
    (net (code "66") (name "Net-(U2-RXOUT19)") (class "Default")
      (node (ref "JP2") (pin "42") (pinfunction "42_42") (pintype "passive"))
      (node (ref "U2") (pin "4") (pinfunction "RXOUT19_4") (pintype "output"))
    )
    (net (code "67") (name "Net-(U2-RXOUT20)") (class "Default")
      (node (ref "JP2") (pin "44") (pinfunction "44_44") (pintype "passive"))
      (node (ref "U2") (pin "5") (pinfunction "RXOUT20_5") (pintype "output"))
    )
    (net (code "68") (name "Net-(U2-~{PWR_DWN})") (class "Default")
      (node (ref "R6") (pin "2") (pinfunction "2_2") (pintype "passive"))
      (node (ref "U2") (pin "22") (pinfunction "~{PWR_DWN}_22") (pintype "input"))
    )
  )
)
